# CHECon.net
KiCad netlist of a schematic drawn in EAGLE
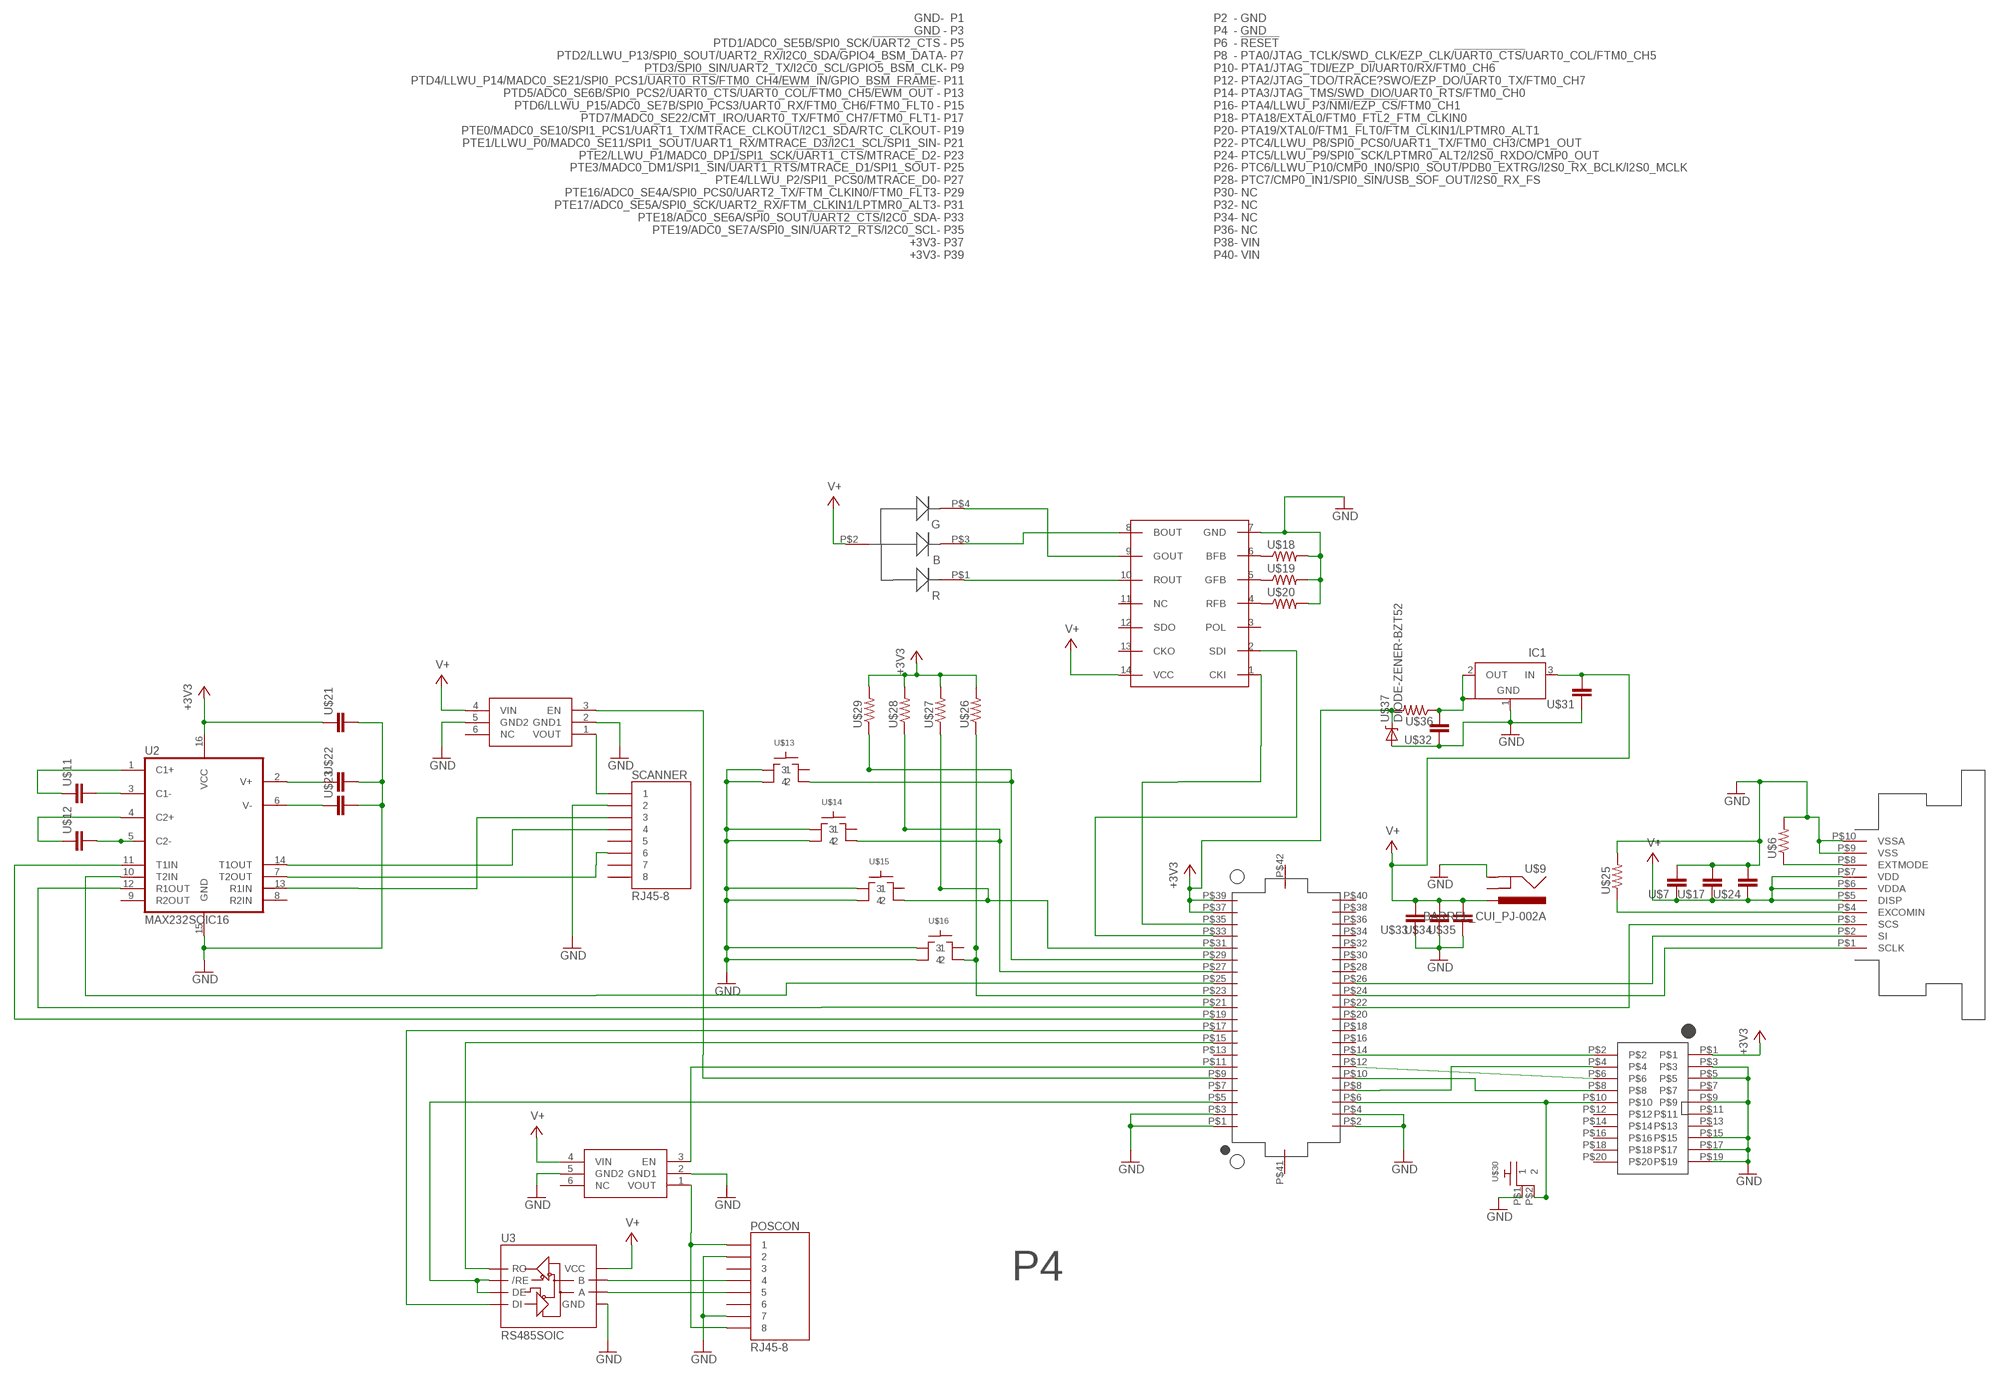
[diagram p0: schematic, sheet 1]

(export (version "E")
  (design (tool "Eeschema 10.0.6"))
  (components
    (comp (ref "IC1")
      (value "NCP1117ST33T3G_1")
      (footprint "eagle-import:SOT223")
      (libsource (lib "eagle-import") (part "NCP1117ST33T3G_1"))
    )
    (comp (ref "POSCON")
      (value "RJ45-8")
      (footprint "eagle-import:MOLEX-0955016649")
      (libsource (lib "eagle-import") (part "RJ45-8"))
    )
    (comp (ref "SCANNER")
      (value "RJ45-8")
      (footprint "eagle-import:MOLEX-0955016649")
      (libsource (lib "eagle-import") (part "RJ45-8"))
    )
    (comp (ref "U$1")
      (value "RGLBED")
      (footprint "eagle-import:RGBLED")
      (libsource (lib "eagle-import") (part "RGLBED"))
    )
    (comp (ref "U$2")
      (value "52745-1097")
      (footprint "eagle-import:52745-1097")
      (libsource (lib "eagle-import") (part "52745-1097"))
    )
    (comp (ref "U$3")
      (value "2X10JTAG")
      (footprint "eagle-import:2X10JTAG")
      (libsource (lib "eagle-import") (part "2X10JTAG"))
    )
    (comp (ref "U$4")
      (value "MIC94061C6")
      (footprint "eagle-import:SC70-6L")
      (libsource (lib "eagle-import") (part "MIC94061C6"))
    )
    (comp (ref "U$5")
      (value "MIC94061C6")
      (footprint "eagle-import:SC70-6L")
      (libsource (lib "eagle-import") (part "MIC94061C6"))
    )
    (comp (ref "U$6")
      (value "RF-R0805")
      (footprint "eagle-import:RF-C0805")
      (libsource (lib "eagle-import") (part "RF-R0805"))
    )
    (comp (ref "U$7")
      (value "RF-C0805")
      (footprint "eagle-import:C0805")
      (libsource (lib "eagle-import") (part "RF-C0805"))
    )
    (comp (ref "U$8")
      (value "WS2801")
      (footprint "eagle-import:SO14")
      (libsource (lib "eagle-import") (part "WS2801"))
    )
    (comp (ref "U$9")
      (value "BARREL_CUI_PJ-002A")
      (footprint "eagle-import:BARREL_CUI_PJ-002A")
      (libsource (lib "eagle-import") (part "BARREL_CUI_PJ-002A"))
    )
    (comp (ref "U$10")
      (value "DF12_F")
      (footprint "eagle-import:DF12_F")
      (libsource (lib "eagle-import") (part "DF12_F"))
    )
    (comp (ref "U$11")
      (value "RF-C0805")
      (footprint "eagle-import:C0805")
      (libsource (lib "eagle-import") (part "RF-C0805"))
    )
    (comp (ref "U$12")
      (value "RF-C0805")
      (footprint "eagle-import:C0805")
      (libsource (lib "eagle-import") (part "RF-C0805"))
    )
    (comp (ref "U$13")
      (value "SWITCH-TACTILE")
      (footprint "eagle-import:ESWITCH-TL3301PF")
      (libsource (lib "eagle-import") (part "SWITCH-TACTILE"))
    )
    (comp (ref "U$14")
      (value "SWITCH-TACTILE")
      (footprint "eagle-import:ESWITCH-TL3301PF")
      (libsource (lib "eagle-import") (part "SWITCH-TACTILE"))
    )
    (comp (ref "U$15")
      (value "SWITCH-TACTILE")
      (footprint "eagle-import:ESWITCH-TL3301PF")
      (libsource (lib "eagle-import") (part "SWITCH-TACTILE"))
    )
    (comp (ref "U$16")
      (value "SWITCH-TACTILE")
      (footprint "eagle-import:ESWITCH-TL3301PF")
      (libsource (lib "eagle-import") (part "SWITCH-TACTILE"))
    )
    (comp (ref "U$17")
      (value "RF-C0805")
      (footprint "eagle-import:C0805")
      (libsource (lib "eagle-import") (part "RF-C0805"))
    )
    (comp (ref "U$18")
      (value "RF-R0805")
      (footprint "eagle-import:RF-C0805")
      (libsource (lib "eagle-import") (part "RF-R0805"))
    )
    (comp (ref "U$19")
      (value "RF-R0805")
      (footprint "eagle-import:RF-C0805")
      (libsource (lib "eagle-import") (part "RF-R0805"))
    )
    (comp (ref "U$20")
      (value "RF-R0805")
      (footprint "eagle-import:RF-C0805")
      (libsource (lib "eagle-import") (part "RF-R0805"))
    )
    (comp (ref "U$21")
      (value "RF-C0805")
      (footprint "eagle-import:C0805")
      (libsource (lib "eagle-import") (part "RF-C0805"))
    )
    (comp (ref "U$22")
      (value "RF-C0805")
      (footprint "eagle-import:C0805")
      (libsource (lib "eagle-import") (part "RF-C0805"))
    )
    (comp (ref "U$23")
      (value "RF-C0805")
      (footprint "eagle-import:C0805")
      (libsource (lib "eagle-import") (part "RF-C0805"))
    )
    (comp (ref "U$24")
      (value "RF-C0805")
      (footprint "eagle-import:C0805")
      (libsource (lib "eagle-import") (part "RF-C0805"))
    )
    (comp (ref "U$25")
      (value "RF-R0805")
      (footprint "eagle-import:RF-C0805")
      (libsource (lib "eagle-import") (part "RF-R0805"))
    )
    (comp (ref "U$26")
      (value "RF-R0805")
      (footprint "eagle-import:RF-C0805")
      (libsource (lib "eagle-import") (part "RF-R0805"))
    )
    (comp (ref "U$27")
      (value "RF-R0805")
      (footprint "eagle-import:RF-C0805")
      (libsource (lib "eagle-import") (part "RF-R0805"))
    )
    (comp (ref "U$28")
      (value "RF-R0805")
      (footprint "eagle-import:RF-C0805")
      (libsource (lib "eagle-import") (part "RF-R0805"))
    )
    (comp (ref "U$29")
      (value "RF-R0805")
      (footprint "eagle-import:RF-C0805")
      (libsource (lib "eagle-import") (part "RF-R0805"))
    )
    (comp (ref "U$30")
      (value "RA_BUTTON")
      (footprint "eagle-import:RA_BUTTON")
      (libsource (lib "eagle-import") (part "RA_BUTTON"))
    )
    (comp (ref "U$31")
      (value "RF-C0805")
      (footprint "eagle-import:C0805")
      (libsource (lib "eagle-import") (part "RF-C0805"))
    )
    (comp (ref "U$32")
      (value "RF-C0805")
      (footprint "eagle-import:C0805")
      (libsource (lib "eagle-import") (part "RF-C0805"))
    )
    (comp (ref "U$33")
      (value "RF-C0805")
      (footprint "eagle-import:C0805")
      (libsource (lib "eagle-import") (part "RF-C0805"))
    )
    (comp (ref "U$34")
      (value "RF-C0805")
      (footprint "eagle-import:C0805")
      (libsource (lib "eagle-import") (part "RF-C0805"))
    )
    (comp (ref "U$35")
      (value "RF-C0805")
      (footprint "eagle-import:C0805")
      (libsource (lib "eagle-import") (part "RF-C0805"))
    )
    (comp (ref "U$36")
      (value "RF-R0805")
      (footprint "eagle-import:RF-C0805")
      (libsource (lib "eagle-import") (part "RF-R0805"))
    )
    (comp (ref "U$37")
      (value "DIODE-ZENER-BZT52")
      (footprint "eagle-import:SOD-323")
      (libsource (lib "eagle-import") (part "DIODE-ZENER-BZT52"))
    )
    (comp (ref "U2")
      (value "MAX232SOIC16")
      (footprint "eagle-import:SO016")
      (libsource (lib "eagle-import") (part "MAX232SOIC16"))
    )
    (comp (ref "U3")
      (value "RS485SOIC")
      (footprint "eagle-import:SO08")
      (libsource (lib "eagle-import") (part "RS485SOIC"))
    )
  )
  (nets
    (net (code "1") (name "+3V3") (class "Default")
      (node (ref "U$10") (pin "P$37") (pinfunction "+3V3_P$37") (pintype "bidirectional"))
      (node (ref "U$10") (pin "P$39") (pinfunction "+3V3_P$39") (pintype "bidirectional"))
      (node (ref "U$21") (pin "1") (pinfunction "1_1") (pintype "passive"))
      (node (ref "U$26") (pin "2") (pinfunction "2_2") (pintype "passive"))
      (node (ref "U$27") (pin "2") (pinfunction "2_2") (pintype "passive"))
      (node (ref "U$28") (pin "2") (pinfunction "2_2") (pintype "passive"))
      (node (ref "U$29") (pin "2") (pinfunction "2_2") (pintype "passive"))
      (node (ref "U$3") (pin "P$1") (pinfunction "P$1_P$1") (pintype "bidirectional"))
      (node (ref "U$36") (pin "2") (pinfunction "2_2") (pintype "passive"))
      (node (ref "U$37") (pin "1") (pinfunction "C_1") (pintype "passive"))
      (node (ref "U2") (pin "16") (pinfunction "VCC_16") (pintype "bidirectional"))
    )
    (net (code "2") (name "GND") (class "Default")
      (node (ref "IC1") (pin "1") (pinfunction "GND_1") (pintype "power_in"))
      (node (ref "POSCON") (pin "P$2") (pinfunction "2_P$2") (pintype "bidirectional"))
      (node (ref "POSCON") (pin "P$7") (pinfunction "7_P$7") (pintype "bidirectional"))
      (node (ref "SCANNER") (pin "P$2") (pinfunction "2_P$2") (pintype "bidirectional"))
      (node (ref "U$10") (pin "P$1") (pinfunction "GND_P$1") (pintype "bidirectional"))
      (node (ref "U$10") (pin "P$2") (pinfunction "GND_P$2") (pintype "bidirectional"))
      (node (ref "U$10") (pin "P$3") (pinfunction "GND_P$3") (pintype "bidirectional"))
      (node (ref "U$10") (pin "P$4") (pinfunction "GND_P$4") (pintype "bidirectional"))
      (node (ref "U$13") (pin "1") (pinfunction "1_1") (pintype "input"))
      (node (ref "U$13") (pin "2") (pinfunction "2_2") (pintype "input"))
      (node (ref "U$14") (pin "1") (pinfunction "1_1") (pintype "input"))
      (node (ref "U$14") (pin "2") (pinfunction "2_2") (pintype "input"))
      (node (ref "U$15") (pin "1") (pinfunction "1_1") (pintype "input"))
      (node (ref "U$15") (pin "2") (pinfunction "2_2") (pintype "input"))
      (node (ref "U$16") (pin "1") (pinfunction "1_1") (pintype "input"))
      (node (ref "U$16") (pin "2") (pinfunction "2_2") (pintype "input"))
      (node (ref "U$17") (pin "2") (pinfunction "2_2") (pintype "passive"))
      (node (ref "U$18") (pin "2") (pinfunction "2_2") (pintype "passive"))
      (node (ref "U$19") (pin "2") (pinfunction "2_2") (pintype "passive"))
      (node (ref "U$2") (pin "P$10") (pinfunction "VSSA_P$10") (pintype "bidirectional"))
      (node (ref "U$2") (pin "P$9") (pinfunction "VSS_P$9") (pintype "bidirectional"))
      (node (ref "U$20") (pin "2") (pinfunction "2_2") (pintype "passive"))
      (node (ref "U$21") (pin "2") (pinfunction "2_2") (pintype "passive"))
      (node (ref "U$22") (pin "2") (pinfunction "2_2") (pintype "passive"))
      (node (ref "U$23") (pin "2") (pinfunction "2_2") (pintype "passive"))
      (node (ref "U$24") (pin "2") (pinfunction "2_2") (pintype "passive"))
      (node (ref "U$25") (pin "2") (pinfunction "2_2") (pintype "passive"))
      (node (ref "U$3") (pin "P$15") (pinfunction "P$15_P$15") (pintype "bidirectional"))
      (node (ref "U$3") (pin "P$17") (pinfunction "P$17_P$17") (pintype "bidirectional"))
      (node (ref "U$3") (pin "P$19") (pinfunction "P$19_P$19") (pintype "bidirectional"))
      (node (ref "U$3") (pin "P$3") (pinfunction "P$3_P$3") (pintype "bidirectional"))
      (node (ref "U$3") (pin "P$5") (pinfunction "P$5_P$5") (pintype "bidirectional"))
      (node (ref "U$3") (pin "P$9") (pinfunction "P$9_P$9") (pintype "bidirectional"))
      (node (ref "U$30") (pin "P$1") (pinfunction "1_P$1") (pintype "input"))
      (node (ref "U$31") (pin "1") (pinfunction "1_1") (pintype "passive"))
      (node (ref "U$32") (pin "1") (pinfunction "1_1") (pintype "passive"))
      (node (ref "U$33") (pin "1") (pinfunction "1_1") (pintype "passive"))
      (node (ref "U$34") (pin "1") (pinfunction "1_1") (pintype "passive"))
      (node (ref "U$35") (pin "1") (pinfunction "1_1") (pintype "passive"))
      (node (ref "U$37") (pin "2") (pinfunction "A_2") (pintype "passive"))
      (node (ref "U$4") (pin "2") (pinfunction "GND1_2") (pintype "bidirectional"))
      (node (ref "U$4") (pin "5") (pinfunction "GND2_5") (pintype "bidirectional"))
      (node (ref "U$5") (pin "2") (pinfunction "GND1_2") (pintype "bidirectional"))
      (node (ref "U$5") (pin "5") (pinfunction "GND2_5") (pintype "bidirectional"))
      (node (ref "U$6") (pin "2") (pinfunction "2_2") (pintype "passive"))
      (node (ref "U$7") (pin "2") (pinfunction "2_2") (pintype "passive"))
      (node (ref "U$8") (pin "7") (pinfunction "GND_7") (pintype "bidirectional"))
      (node (ref "U$9") (pin "P$2") (pinfunction "GND_P$2") (pintype "bidirectional"))
      (node (ref "U2") (pin "15") (pinfunction "GND_15") (pintype "bidirectional"))
      (node (ref "U3") (pin "5") (pinfunction "GND_5") (pintype "bidirectional"))
    )
    (net (code "3") (name "Net-(IC1-OUT)") (class "Default")
      (node (ref "IC1") (pin "2") (pinfunction "OUT_2") (pintype "power_in"))
      (node (ref "IC1") (pin "4") (pinfunction "OUT1_4") (pintype "power_in"))
      (node (ref "U$32") (pin "2") (pinfunction "2_2") (pintype "passive"))
      (node (ref "U$36") (pin "1") (pinfunction "1_1") (pintype "passive"))
    )
    (net (code "4") (name "Net-(POSCON-1)") (class "Default")
      (node (ref "POSCON") (pin "P$1") (pinfunction "1_P$1") (pintype "bidirectional"))
      (node (ref "POSCON") (pin "P$8") (pinfunction "8_P$8") (pintype "bidirectional"))
      (node (ref "U$5") (pin "1") (pinfunction "VOUT_1") (pintype "bidirectional"))
    )
    (net (code "5") (name "Net-(POSCON-4)") (class "Default")
      (node (ref "POSCON") (pin "P$4") (pinfunction "4_P$4") (pintype "bidirectional"))
      (node (ref "U3") (pin "7") (pinfunction "B_7") (pintype "bidirectional"))
    )
    (net (code "6") (name "Net-(POSCON-5)") (class "Default")
      (node (ref "POSCON") (pin "P$5") (pinfunction "5_P$5") (pintype "bidirectional"))
      (node (ref "U3") (pin "6") (pinfunction "A_6") (pintype "bidirectional"))
    )
    (net (code "7") (name "Net-(SCANNER-1)") (class "Default")
      (node (ref "SCANNER") (pin "P$1") (pinfunction "1_P$1") (pintype "bidirectional"))
      (node (ref "U$4") (pin "1") (pinfunction "VOUT_1") (pintype "bidirectional"))
    )
    (net (code "8") (name "Net-(SCANNER-3)") (class "Default")
      (node (ref "SCANNER") (pin "P$3") (pinfunction "3_P$3") (pintype "bidirectional"))
      (node (ref "U2") (pin "13") (pinfunction "R1IN_13") (pintype "input"))
    )
    (net (code "9") (name "Net-(SCANNER-4)") (class "Default")
      (node (ref "SCANNER") (pin "P$4") (pinfunction "4_P$4") (pintype "bidirectional"))
      (node (ref "U2") (pin "14") (pinfunction "T1OUT_14") (pintype "output"))
    )
    (net (code "10") (name "Net-(SCANNER-6)") (class "Default")
      (node (ref "SCANNER") (pin "P$6") (pinfunction "6_P$6") (pintype "bidirectional"))
      (node (ref "U2") (pin "7") (pinfunction "T2OUT_7") (pintype "output"))
    )
    (net (code "11") (name "Net-(U$1-BLUE)") (class "Default")
      (node (ref "U$1") (pin "P$3") (pinfunction "BLUE_P$3") (pintype "bidirectional"))
      (node (ref "U$8") (pin "8") (pinfunction "BOUT_8") (pintype "bidirectional"))
    )
    (net (code "12") (name "Net-(U$1-GREEN)") (class "Default")
      (node (ref "U$1") (pin "P$4") (pinfunction "GREEN_P$4") (pintype "bidirectional"))
      (node (ref "U$8") (pin "9") (pinfunction "GOUT_9") (pintype "bidirectional"))
    )
    (net (code "13") (name "Net-(U$1-RED)") (class "Default")
      (node (ref "U$1") (pin "P$1") (pinfunction "RED_P$1") (pintype "bidirectional"))
      (node (ref "U$8") (pin "10") (pinfunction "ROUT_10") (pintype "bidirectional"))
    )
    (net (code "14") (name "Net-(U$2-EXCOMIN)") (class "Default")
      (node (ref "U$2") (pin "P$4") (pinfunction "EXCOMIN_P$4") (pintype "bidirectional"))
      (node (ref "U$25") (pin "1") (pinfunction "1_1") (pintype "passive"))
    )
    (net (code "15") (name "Net-(U$2-EXTMODE)") (class "Default")
      (node (ref "U$2") (pin "P$8") (pinfunction "EXTMODE_P$8") (pintype "bidirectional"))
      (node (ref "U$6") (pin "1") (pinfunction "1_1") (pintype "passive"))
    )
    (net (code "16") (name "Net-(U$8-BFB)") (class "Default")
      (node (ref "U$18") (pin "1") (pinfunction "1_1") (pintype "passive"))
      (node (ref "U$8") (pin "6") (pinfunction "BFB_6") (pintype "bidirectional"))
    )
    (net (code "17") (name "Net-(U$8-GFB)") (class "Default")
      (node (ref "U$19") (pin "1") (pinfunction "1_1") (pintype "passive"))
      (node (ref "U$8") (pin "5") (pinfunction "GFB_5") (pintype "bidirectional"))
    )
    (net (code "18") (name "Net-(U$8-RFB)") (class "Default")
      (node (ref "U$20") (pin "1") (pinfunction "1_1") (pintype "passive"))
      (node (ref "U$8") (pin "4") (pinfunction "RFB_4") (pintype "bidirectional"))
    )
    (net (code "19") (name "Net-(U$10-PTA0{slash}JTAG_TCLK{slash}SWD_CLK{slash}EZP_CLK{slash}~{UART0_CTS{slash}}UART0_COL{slash}FTM0_CH5)") (class "Default")
      (node (ref "U$10") (pin "P$8") (pinfunction "PTA0/JTAG_TCLK/SWD_CLK/EZP_CLK/~{UART0_CTS/}UART0_COL/FTM0_CH5_P$8") (pintype "bidirectional"))
      (node (ref "U$3") (pin "P$4") (pinfunction "P$4_P$4") (pintype "bidirectional"))
    )
    (net (code "20") (name "Net-(U$10-PTA1{slash}JTAG_TDI{slash}EZP_DI{slash}UART0{slash}RX{slash}FTM0_CH6)") (class "Default")
      (node (ref "U$10") (pin "P$10") (pinfunction "PTA1/JTAG_TDI/EZP_DI/UART0/RX/FTM0_CH6_P$10") (pintype "bidirectional"))
      (node (ref "U$3") (pin "P$8") (pinfunction "P$8_P$8") (pintype "bidirectional"))
    )
    (net (code "21") (name "Net-(U$10-PTA2{slash}JTAG_TDO{slash}TRACE?SWO{slash}EZP_DO{slash}UART0_TX{slash}FTM0_CH7)") (class "Default")
      (node (ref "U$10") (pin "P$12") (pinfunction "PTA2/JTAG_TDO/TRACE?SWO/EZP_DO/UART0_TX/FTM0_CH7_P$12") (pintype "bidirectional"))
      (node (ref "U$3") (pin "P$6") (pinfunction "P$6_P$6") (pintype "bidirectional"))
    )
    (net (code "22") (name "Net-(U$10-PTA3{slash}JTAG_TMS{slash}SWD_DIO{slash}UART0_RTS{slash}FTM0_CH0)") (class "Default")
      (node (ref "U$10") (pin "P$14") (pinfunction "PTA3/JTAG_TMS/SWD_DIO/UART0_RTS/FTM0_CH0_P$14") (pintype "bidirectional"))
      (node (ref "U$3") (pin "P$2") (pinfunction "P$2_P$2") (pintype "bidirectional"))
    )
    (net (code "23") (name "Net-(U$10-PTC4{slash}LLWU_P8{slash}SPI0_PCS0{slash}UART1_TX{slash}FTM0_CH3{slash}CMP1_OUT)") (class "Default")
      (node (ref "U$10") (pin "P$22") (pinfunction "PTC4/LLWU_P8/SPI0_PCS0/UART1_TX/FTM0_CH3/CMP1_OUT_P$22") (pintype "bidirectional"))
      (node (ref "U$2") (pin "P$3") (pinfunction "SCS_P$3") (pintype "bidirectional"))
    )
    (net (code "24") (name "Net-(U$10-PTC5{slash}LLWU_P8{slash}SPI0_PCS0{slash}UART1_TX{slash}FTM0_CH3{slash}CMP1_OUT)") (class "Default")
      (node (ref "U$10") (pin "P$24") (pinfunction "PTC5/LLWU_P8/SPI0_PCS0/UART1_TX/FTM0_CH3/CMP1_OUT_P$24") (pintype "bidirectional"))
      (node (ref "U$2") (pin "P$1") (pinfunction "SCLK_P$1") (pintype "bidirectional"))
    )
    (net (code "25") (name "Net-(U$10-PTC6{slash}LLWU_P10{slash}CMP0_IN0{slash}SPI0_SOUT{slash}PDB0_EXTRG{slash}I2S0_RX_BCLK{slash}I2S0_MCLK)") (class "Default")
      (node (ref "U$10") (pin "P$26") (pinfunction "PTC6/LLWU_P10/CMP0_IN0/SPI0_SOUT/PDB0_EXTRG/I2S0_RX_BCLK/I2S0_MCLK_P$26") (pintype "bidirectional"))
      (node (ref "U$2") (pin "P$2") (pinfunction "SI_P$2") (pintype "bidirectional"))
    )
    (net (code "26") (name "Net-(U$10-PTD1{slash}ADC0_SE5B{slash}SPI0_SCK{slash}~{UART2_CTS})") (class "Default")
      (node (ref "U$10") (pin "P$5") (pinfunction "PTD1/ADC0_SE5B/SPI0_SCK/~{UART2_CTS}_P$5") (pintype "bidirectional"))
      (node (ref "U3") (pin "2") (pinfunction "/RE_2") (pintype "bidirectional"))
      (node (ref "U3") (pin "3") (pinfunction "DE_3") (pintype "bidirectional"))
    )
    (net (code "27") (name "Net-(U$10-PTD3{slash}SPI0_SIN{slash}UART2_TX{slash}I2C0_SCL{slash}GPIO5_BSM_CLK)") (class "Default")
      (node (ref "U$10") (pin "P$9") (pinfunction "PTD3/SPI0_SIN/UART2_TX/I2C0_SCL/GPIO5_BSM_CLK_P$9") (pintype "bidirectional"))
      (node (ref "U$4") (pin "3") (pinfunction "EN_3") (pintype "bidirectional"))
    )
    (net (code "28") (name "Net-(U$10-PTD4{slash}LLWU_P14{slash}MADC0_SE21{slash}SPI0_PCS1{slash}~{UART0_RTS}{slash}FTM0_CH4{slash}EWM_IN{slash}GPIO_BSM_FRAME)") (class "Default")
      (node (ref "U$10") (pin "P$11") (pinfunction "PTD4/LLWU_P14/MADC0_SE21/SPI0_PCS1/~{UART0_RTS}/FTM0_CH4/EWM_IN/GPIO_BSM_FRAME_P$11") (pintype "bidirectional"))
      (node (ref "U$5") (pin "3") (pinfunction "EN_3") (pintype "bidirectional"))
    )
    (net (code "29") (name "Net-(U$10-PTD6{slash}LLWU_P15{slash}ADC0_SE7B{slash}SPI0_PCS3{slash}UART0_RX{slash}FTM0_CH6{slash}FTM0_FLT0)") (class "Default")
      (node (ref "U$10") (pin "P$15") (pinfunction "PTD6/LLWU_P15/ADC0_SE7B/SPI0_PCS3/UART0_RX/FTM0_CH6/FTM0_FLT0_P$15") (pintype "bidirectional"))
      (node (ref "U3") (pin "1") (pinfunction "RO_1") (pintype "bidirectional"))
    )
    (net (code "30") (name "Net-(U$10-PTD7{slash}MADC0_SE22{slash}CMT_IRO{slash}UART0_TX{slash}FTM0_CH7{slash}FTM0_FLT1)") (class "Default")
      (node (ref "U$10") (pin "P$17") (pinfunction "PTD7/MADC0_SE22/CMT_IRO/UART0_TX/FTM0_CH7/FTM0_FLT1_P$17") (pintype "bidirectional"))
      (node (ref "U3") (pin "4") (pinfunction "DI_4") (pintype "bidirectional"))
    )
    (net (code "31") (name "Net-(U$10-PTE0{slash}MADC0_SE10{slash}SPI1_PCS1{slash}UART1_TX{slash}MTRACE_CLKOUT{slash}I2C1_SDA{slash}RTC_CLKOUT)") (class "Default")
      (node (ref "U$10") (pin "P$19") (pinfunction "PTE0/MADC0_SE10/SPI1_PCS1/UART1_TX/MTRACE_CLKOUT/I2C1_SDA/RTC_CLKOUT_P$19") (pintype "bidirectional"))
      (node (ref "U2") (pin "11") (pinfunction "T1IN_11") (pintype "input"))
    )
    (net (code "32") (name "Net-(U$10-PTE1{slash}LLWU_P0{slash}MADC0_SE11{slash}SPI1_SOUT{slash}UART1_RX{slash}MTRACE_D3{slash}I2C1_SCL{slash}SPI1_SIN)") (class "Default")
      (node (ref "U$10") (pin "P$21") (pinfunction "PTE1/LLWU_P0/MADC0_SE11/SPI1_SOUT/UART1_RX/MTRACE_D3/I2C1_SCL/SPI1_SIN_P$21") (pintype "bidirectional"))
      (node (ref "U2") (pin "12") (pinfunction "R1OUT_12") (pintype "output"))
    )
    (net (code "33") (name "Net-(U$10-PTE2{slash}LLWU_P1{slash}MADC0_DP1{slash}SPI1_SCK{slash}~{UART1_CTS}{slash}MTRACE_D2)") (class "Default")
      (node (ref "U$10") (pin "P$23") (pinfunction "PTE2/LLWU_P1/MADC0_DP1/SPI1_SCK/~{UART1_CTS}/MTRACE_D2_P$23") (pintype "bidirectional"))
      (node (ref "U$16") (pin "4") (pinfunction "4_4") (pintype "input"))
      (node (ref "U$26") (pin "1") (pinfunction "1_1") (pintype "passive"))
    )
    (net (code "34") (name "Net-(U$10-PTE3{slash}MADC0_DM1{slash}SPI1_SIN{slash}~{UART1_RTS}{slash}MTRACE_D1{slash}SPI1_SOUT)") (class "Default")
      (node (ref "U$10") (pin "P$25") (pinfunction "PTE3/MADC0_DM1/SPI1_SIN/~{UART1_RTS}/MTRACE_D1/SPI1_SOUT_P$25") (pintype "bidirectional"))
      (node (ref "U2") (pin "10") (pinfunction "T2IN_10") (pintype "input"))
    )
    (net (code "35") (name "Net-(U$10-PTE4{slash}LLWU_P2{slash}SPI1_PCS0{slash}MTRACE_D0)") (class "Default")
      (node (ref "U$10") (pin "P$27") (pinfunction "PTE4/LLWU_P2/SPI1_PCS0/MTRACE_D0_P$27") (pintype "bidirectional"))
      (node (ref "U$14") (pin "4") (pinfunction "4_4") (pintype "input"))
      (node (ref "U$28") (pin "1") (pinfunction "1_1") (pintype "passive"))
    )
    (net (code "36") (name "Net-(U$10-PTE16{slash}ADC0_SE4A{slash}SPI0_PCS0{slash}UART2_TX{slash}FTM_CLKIN0{slash}FTM0_FLT3)") (class "Default")
      (node (ref "U$10") (pin "P$29") (pinfunction "PTE16/ADC0_SE4A/SPI0_PCS0/UART2_TX/FTM_CLKIN0/FTM0_FLT3_P$29") (pintype "bidirectional"))
      (node (ref "U$13") (pin "4") (pinfunction "4_4") (pintype "input"))
      (node (ref "U$29") (pin "1") (pinfunction "1_1") (pintype "passive"))
    )
    (net (code "37") (name "Net-(U$10-PTE17{slash}ADC0_SE5A{slash}SPI0_SCK{slash}UART2_RX{slash}FTM_CLKIN1{slash}LPTMR0_ALT3)") (class "Default")
      (node (ref "U$10") (pin "P$31") (pinfunction "PTE17/ADC0_SE5A/SPI0_SCK/UART2_RX/FTM_CLKIN1/LPTMR0_ALT3_P$31") (pintype "bidirectional"))
      (node (ref "U$15") (pin "4") (pinfunction "4_4") (pintype "input"))
      (node (ref "U$27") (pin "1") (pinfunction "1_1") (pintype "passive"))
    )
    (net (code "38") (name "Net-(U$10-PTE18{slash}ADC0_SE6A{slash}SPI0_SOUT{slash}~{UART2_CTS}{slash}I2C0_SDA)") (class "Default")
      (node (ref "U$10") (pin "P$33") (pinfunction "PTE18/ADC0_SE6A/SPI0_SOUT/~{UART2_CTS}/I2C0_SDA_P$33") (pintype "bidirectional"))
      (node (ref "U$8") (pin "2") (pinfunction "SDI_2") (pintype "bidirectional"))
    )
    (net (code "39") (name "Net-(U$10-PTE19{slash}ADC0_SE7A{slash}SPI0_SIN{slash}~{UART2_RTS}{slash}I2C0_SCL)") (class "Default")
      (node (ref "U$10") (pin "P$35") (pinfunction "PTE19/ADC0_SE7A/SPI0_SIN/~{UART2_RTS}/I2C0_SCL_P$35") (pintype "bidirectional"))
      (node (ref "U$8") (pin "1") (pinfunction "CKI_1") (pintype "bidirectional"))
    )
    (net (code "40") (name "Net-(U$10-~{RESET})") (class "Default")
      (node (ref "U$10") (pin "P$6") (pinfunction "~{RESET}_P$6") (pintype "bidirectional"))
      (node (ref "U$3") (pin "P$10") (pinfunction "P$10_P$10") (pintype "bidirectional"))
      (node (ref "U$30") (pin "P$2") (pinfunction "2_P$2") (pintype "input"))
    )
    (net (code "41") (name "Net-(U2-C1+)") (class "Default")
      (node (ref "U$11") (pin "1") (pinfunction "1_1") (pintype "passive"))
      (node (ref "U2") (pin "1") (pinfunction "C1+_1") (pintype "bidirectional"))
    )
    (net (code "42") (name "Net-(U2-C1-)") (class "Default")
      (node (ref "U$11") (pin "2") (pinfunction "2_2") (pintype "passive"))
      (node (ref "U2") (pin "3") (pinfunction "C1-_3") (pintype "bidirectional"))
    )
    (net (code "43") (name "Net-(U2-C2+)") (class "Default")
      (node (ref "U$12") (pin "1") (pinfunction "1_1") (pintype "passive"))
      (node (ref "U2") (pin "4") (pinfunction "C2+_4") (pintype "bidirectional"))
    )
    (net (code "44") (name "Net-(U2-C2-)") (class "Default")
      (node (ref "U$12") (pin "2") (pinfunction "2_2") (pintype "passive"))
      (node (ref "U2") (pin "5") (pinfunction "C2-_5") (pintype "bidirectional"))
    )
    (net (code "45") (name "Net-(U2-V+)") (class "Default")
      (node (ref "U$22") (pin "1") (pinfunction "1_1") (pintype "passive"))
      (node (ref "U2") (pin "2") (pinfunction "V+_2") (pintype "bidirectional"))
    )
    (net (code "46") (name "Net-(U2-V-)") (class "Default")
      (node (ref "U$23") (pin "1") (pinfunction "1_1") (pintype "passive"))
      (node (ref "U2") (pin "6") (pinfunction "V-_6") (pintype "bidirectional"))
    )
    (net (code "47") (name "V+") (class "Default")
      (node (ref "IC1") (pin "3") (pinfunction "IN_3") (pintype "input"))
      (node (ref "U$1") (pin "P$2") (pinfunction "ANODE_P$2") (pintype "bidirectional"))
      (node (ref "U$17") (pin "1") (pinfunction "1_1") (pintype "passive"))
      (node (ref "U$2") (pin "P$5") (pinfunction "DISP_P$5") (pintype "bidirectional"))
      (node (ref "U$2") (pin "P$6") (pinfunction "VDDA_P$6") (pintype "bidirectional"))
      (node (ref "U$2") (pin "P$7") (pinfunction "VDD_P$7") (pintype "bidirectional"))
      (node (ref "U$24") (pin "1") (pinfunction "1_1") (pintype "passive"))
      (node (ref "U$31") (pin "2") (pinfunction "2_2") (pintype "passive"))
      (node (ref "U$33") (pin "2") (pinfunction "2_2") (pintype "passive"))
      (node (ref "U$34") (pin "2") (pinfunction "2_2") (pintype "passive"))
      (node (ref "U$35") (pin "2") (pinfunction "2_2") (pintype "passive"))
      (node (ref "U$4") (pin "4") (pinfunction "VIN_4") (pintype "bidirectional"))
      (node (ref "U$5") (pin "4") (pinfunction "VIN_4") (pintype "bidirectional"))
      (node (ref "U$7") (pin "1") (pinfunction "1_1") (pintype "passive"))
      (node (ref "U$8") (pin "14") (pinfunction "VCC_14") (pintype "bidirectional"))
      (node (ref "U$9") (pin "P$1") (pinfunction "PWR_P$1") (pintype "bidirectional"))
      (node (ref "U3") (pin "8") (pinfunction "VCC_8") (pintype "bidirectional"))
    )
    (net (code "48") (name "unconnected-(POSCON-3-PadP$3)") (class "Default")
      (node (ref "POSCON") (pin "P$3") (pinfunction "3_P$3") (pintype "bidirectional"))
    )
    (net (code "49") (name "unconnected-(POSCON-6-PadP$6)") (class "Default")
      (node (ref "POSCON") (pin "P$6") (pinfunction "6_P$6") (pintype "bidirectional"))
    )
    (net (code "50") (name "unconnected-(SCANNER-5-PadP$5)") (class "Default")
      (node (ref "SCANNER") (pin "P$5") (pinfunction "5_P$5") (pintype "bidirectional"))
    )
    (net (code "51") (name "unconnected-(SCANNER-7-PadP$7)") (class "Default")
      (node (ref "SCANNER") (pin "P$7") (pinfunction "7_P$7") (pintype "bidirectional"))
    )
    (net (code "52") (name "unconnected-(SCANNER-8-PadP$8)") (class "Default")
      (node (ref "SCANNER") (pin "P$8") (pinfunction "8_P$8") (pintype "bidirectional"))
    )
    (net (code "53") (name "unconnected-(U$3-PadP$7)") (class "Default")
      (node (ref "U$3") (pin "P$7") (pinfunction "P$7_P$7") (pintype "bidirectional"))
    )
    (net (code "54") (name "unconnected-(U$3-PadP$11)") (class "Default")
      (node (ref "U$3") (pin "P$11") (pinfunction "P$11_P$11") (pintype "bidirectional"))
    )
    (net (code "55") (name "unconnected-(U$3-PadP$12)") (class "Default")
      (node (ref "U$3") (pin "P$12") (pinfunction "P$12_P$12") (pintype "bidirectional"))
    )
    (net (code "56") (name "unconnected-(U$3-PadP$13)") (class "Default")
      (node (ref "U$3") (pin "P$13") (pinfunction "P$13_P$13") (pintype "bidirectional"))
    )
    (net (code "57") (name "unconnected-(U$3-PadP$14)") (class "Default")
      (node (ref "U$3") (pin "P$14") (pinfunction "P$14_P$14") (pintype "bidirectional"))
    )
    (net (code "58") (name "unconnected-(U$3-PadP$16)") (class "Default")
      (node (ref "U$3") (pin "P$16") (pinfunction "P$16_P$16") (pintype "bidirectional"))
    )
    (net (code "59") (name "unconnected-(U$3-PadP$18)") (class "Default")
      (node (ref "U$3") (pin "P$18") (pinfunction "P$18_P$18") (pintype "bidirectional"))
    )
    (net (code "60") (name "unconnected-(U$3-PadP$20)") (class "Default")
      (node (ref "U$3") (pin "P$20") (pinfunction "P$20_P$20") (pintype "bidirectional"))
    )
    (net (code "61") (name "unconnected-(U$4-NC-Pad6)") (class "Default")
      (node (ref "U$4") (pin "6") (pinfunction "NC_6") (pintype "bidirectional"))
    )
    (net (code "62") (name "unconnected-(U$5-NC-Pad6)") (class "Default")
      (node (ref "U$5") (pin "6") (pinfunction "NC_6") (pintype "bidirectional"))
    )
    (net (code "63") (name "unconnected-(U$8-CKO-Pad13)") (class "Default")
      (node (ref "U$8") (pin "13") (pinfunction "CKO_13") (pintype "bidirectional"))
    )
    (net (code "64") (name "unconnected-(U$8-NC-Pad11)") (class "Default")
      (node (ref "U$8") (pin "11") (pinfunction "NC_11") (pintype "bidirectional"))
    )
    (net (code "65") (name "unconnected-(U$8-POL-Pad3)") (class "Default")
      (node (ref "U$8") (pin "3") (pinfunction "POL_3") (pintype "bidirectional"))
    )
    (net (code "66") (name "unconnected-(U$8-SDO-Pad12)") (class "Default")
      (node (ref "U$8") (pin "12") (pinfunction "SDO_12") (pintype "bidirectional"))
    )
    (net (code "67") (name "unconnected-(U$9-GNDBREAK-PadP$3)") (class "Default")
      (node (ref "U$9") (pin "P$3") (pinfunction "GNDBREAK_P$3") (pintype "bidirectional"))
    )
    (net (code "68") (name "unconnected-(U$10-NC-PadP$30)") (class "Default")
      (node (ref "U$10") (pin "P$30") (pinfunction "NC_P$30") (pintype "bidirectional"))
    )
    (net (code "69") (name "unconnected-(U$10-NC-PadP$32)") (class "Default")
      (node (ref "U$10") (pin "P$32") (pinfunction "NC_P$32") (pintype "bidirectional"))
    )
    (net (code "70") (name "unconnected-(U$10-NC-PadP$34)") (class "Default")
      (node (ref "U$10") (pin "P$34") (pinfunction "NC_P$34") (pintype "bidirectional"))
    )
    (net (code "71") (name "unconnected-(U$10-NC-PadP$36)") (class "Default")
      (node (ref "U$10") (pin "P$36") (pinfunction "NC_P$36") (pintype "bidirectional"))
    )
    (net (code "72") (name "unconnected-(U$10-PTA4{slash}LLWU_P3{slash}~{NMI}{slash}~{EZP_CS}{slash}FTM0_CH1-PadP$16)") (class "Default")
      (node (ref "U$10") (pin "P$16") (pinfunction "PTA4/LLWU_P3/~{NMI}/~{EZP_CS}/FTM0_CH1_P$16") (pintype "bidirectional"))
    )
    (net (code "73") (name "unconnected-(U$10-PTA18{slash}EXTAL0{slash}FTM0_FTL2_FTM_CLKIN0-PadP$18)") (class "Default")
      (node (ref "U$10") (pin "P$18") (pinfunction "PTA18/EXTAL0/FTM0_FTL2_FTM_CLKIN0_P$18") (pintype "bidirectional"))
    )
    (net (code "74") (name "unconnected-(U$10-PTA19{slash}XTAL0{slash}FTM1_FLT0{slash}FTM_CLKIN1{slash}LPTMR0_ALT1-PadP$20)") (class "Default")
      (node (ref "U$10") (pin "P$20") (pinfunction "PTA19/XTAL0/FTM1_FLT0/FTM_CLKIN1/LPTMR0_ALT1_P$20") (pintype "bidirectional"))
    )
    (net (code "75") (name "unconnected-(U$10-PTC7{slash}CMP0_IN1{slash}SPI0_SIN{slash}USB_SOF_OUT{slash}I2S0_RX_FS-PadP$28)") (class "Default")
      (node (ref "U$10") (pin "P$28") (pinfunction "PTC7/CMP0_IN1/SPI0_SIN/USB_SOF_OUT/I2S0_RX_FS_P$28") (pintype "bidirectional"))
    )
    (net (code "76") (name "unconnected-(U$10-PTD2{slash}LLWU_P13{slash}SPI0_SOUT{slash}UART2_RX{slash}I2C0_SDA{slash}GPIO4_BSM_DATA-PadP$7)") (class "Default")
      (node (ref "U$10") (pin "P$7") (pinfunction "PTD2/LLWU_P13/SPI0_SOUT/UART2_RX/I2C0_SDA/GPIO4_BSM_DATA_P$7") (pintype "bidirectional"))
    )
    (net (code "77") (name "unconnected-(U$10-PTD5{slash}ADC0_SE6B{slash}SPI0_PCS2{slash}~{UART0_CTS}{slash}~{UART0_COL}{slash}FTM0_CH5{slash}~{EWM_OUT}-PadP$13)") (class "Default")
      (node (ref "U$10") (pin "P$13") (pinfunction "PTD5/ADC0_SE6B/SPI0_PCS2/~{UART0_CTS}/~{UART0_COL}/FTM0_CH5/~{EWM_OUT}_P$13") (pintype "bidirectional"))
    )
    (net (code "78") (name "unconnected-(U$10-PadP$41)") (class "Default")
      (node (ref "U$10") (pin "P$41") (pinfunction "P$41_P$41") (pintype "bidirectional"))
    )
    (net (code "79") (name "unconnected-(U$10-PadP$42)") (class "Default")
      (node (ref "U$10") (pin "P$42") (pinfunction "P$42_P$42") (pintype "bidirectional"))
    )
    (net (code "80") (name "unconnected-(U$10-VIN-PadP$38)") (class "Default")
      (node (ref "U$10") (pin "P$38") (pinfunction "VIN_P$38") (pintype "bidirectional"))
    )
    (net (code "81") (name "unconnected-(U$10-VIN-PadP$40)") (class "Default")
      (node (ref "U$10") (pin "P$40") (pinfunction "VIN_P$40") (pintype "bidirectional"))
    )
    (net (code "82") (name "unconnected-(U$13-Pad3)") (class "Default")
      (node (ref "U$13") (pin "3") (pinfunction "3_3") (pintype "input"))
    )
    (net (code "83") (name "unconnected-(U$14-Pad3)") (class "Default")
      (node (ref "U$14") (pin "3") (pinfunction "3_3") (pintype "input"))
    )
    (net (code "84") (name "unconnected-(U$15-Pad3)") (class "Default")
      (node (ref "U$15") (pin "3") (pinfunction "3_3") (pintype "input"))
    )
    (net (code "85") (name "unconnected-(U$16-Pad3)") (class "Default")
      (node (ref "U$16") (pin "3") (pinfunction "3_3") (pintype "input"))
    )
    (net (code "86") (name "unconnected-(U2-R2IN-Pad8)") (class "Default")
      (node (ref "U2") (pin "8") (pinfunction "R2IN_8") (pintype "input"))
    )
    (net (code "87") (name "unconnected-(U2-R2OUT-Pad9)") (class "Default")
      (node (ref "U2") (pin "9") (pinfunction "R2OUT_9") (pintype "output"))
    )
  )
)
